# 01_MAIN.net
KiCad netlist of a schematic drawn in Altium Designer
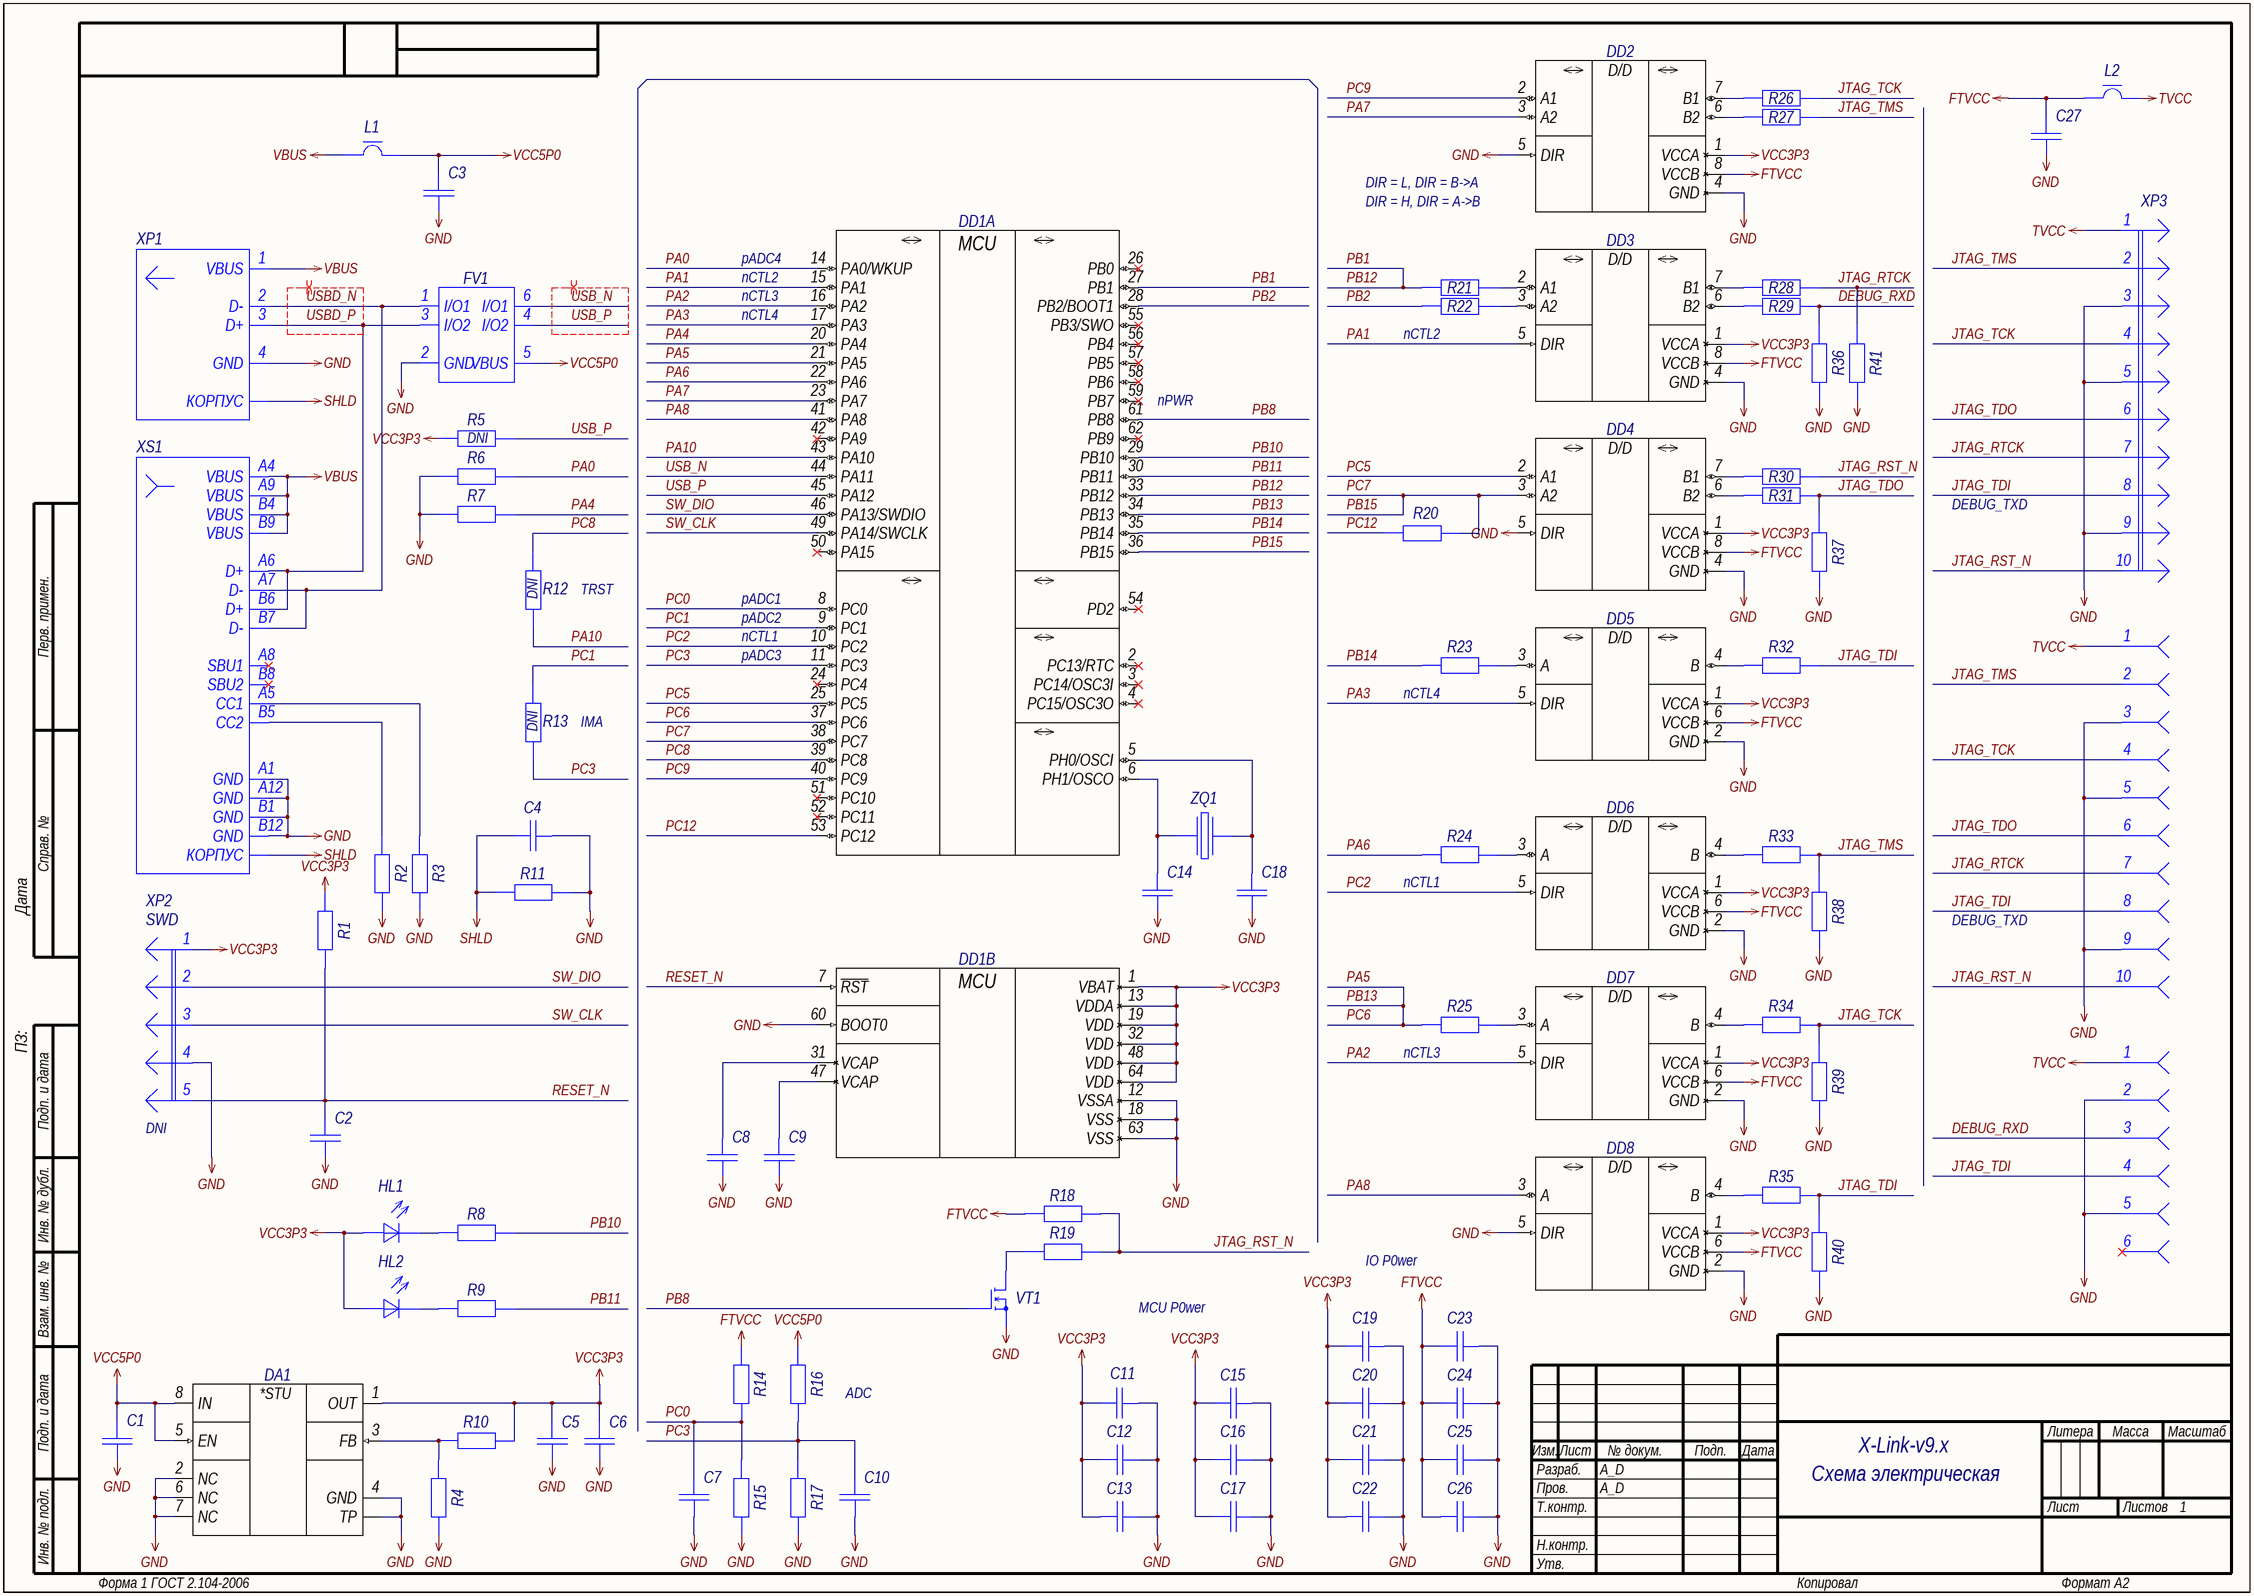
[diagram p0: 01_MAIN.SchDoc]

(export (version "E")
  (design (tool "Eeschema 10.0.6"))
  (components
    (comp (ref "C1")
      (value "Capacitor")
      (footprint "C0402_L")
      (fields
        (field (name "PART NUMBER") "GRM155R61C105KA12D")
        (field (name "VOLTAGE") "16V")
        (field (name "TOLERANCE") "±10%")
        (field (name "PUBLISHER") "Andrew Danich")
      )
      (libsource (lib "ADLib") (part "Capacitor"))
    )
    (comp (ref "C2")
      (value "~")
      (footprint "C0402_L")
      (fields
        (field (name "PART NUMBER") "GCM155R71C104KA55D")
        (field (name "VOLTAGE") "16V")
        (field (name "TOLERANCE") "±10%")
        (field (name "PUBLISHER") "Andrew Danich")
      )
      (libsource (lib "ADLib") (part "Capacitor"))
    )
    (comp (ref "C3")
      (value "Capacitor")
      (footprint "C0603_L")
      (fields
        (field (name "PART NUMBER") "GRM188R61A106KE69D")
        (field (name "VOLTAGE") "10V")
        (field (name "TOLERANCE") "±10%")
        (field (name "PUBLISHER") "Andrew Danich")
      )
      (libsource (lib "ADLib") (part "Capacitor"))
    )
    (comp (ref "C4")
      (value "~")
      (footprint "C0402_L")
      (fields
        (field (name "PART NUMBER") "GCM155R71C104KA55D")
        (field (name "VOLTAGE") "16V")
        (field (name "TOLERANCE") "±10%")
        (field (name "PUBLISHER") "Andrew Danich")
      )
      (libsource (lib "ADLib") (part "Capacitor"))
    )
    (comp (ref "C5")
      (value "Capacitor")
      (footprint "C0402_L")
      (fields
        (field (name "PART NUMBER") "GRM155R60J475ME87D")
        (field (name "VOLTAGE") "6.3V")
        (field (name "TOLERANCE") "±20%")
        (field (name "PUBLISHER") "Andrew Danich")
      )
      (libsource (lib "ADLib") (part "Capacitor"))
    )
    (comp (ref "C6")
      (value "Capacitor")
      (footprint "C0402_L")
      (fields
        (field (name "PART NUMBER") "GRM155R60J475ME87D")
        (field (name "VOLTAGE") "6.3V")
        (field (name "TOLERANCE") "±20%")
        (field (name "PUBLISHER") "Andrew Danich")
      )
      (libsource (lib "ADLib") (part "Capacitor"))
    )
    (comp (ref "C7")
      (value "Capacitor")
      (footprint "C0402_L")
      (fields
        (field (name "PART NUMBER") "GCM155R71E103KA37D")
        (field (name "VOLTAGE") "25V")
        (field (name "TOLERANCE") "±10%")
        (field (name "PUBLISHER") "Andrew Danich")
      )
      (libsource (lib "ADLib") (part "Capacitor"))
    )
    (comp (ref "C8")
      (value "Capacitor")
      (footprint "C0402_L")
      (fields
        (field (name "PART NUMBER") "GRM155D71C225ME11D")
        (field (name "VOLTAGE") "16V")
        (field (name "TOLERANCE") "±20%")
        (field (name "PUBLISHER") "Andrew Danich")
      )
      (libsource (lib "ADLib") (part "Capacitor"))
    )
    (comp (ref "C9")
      (value "Capacitor")
      (footprint "C0402_L")
      (fields
        (field (name "PART NUMBER") "GRM155D71C225ME11D")
        (field (name "VOLTAGE") "16V")
        (field (name "TOLERANCE") "±20%")
        (field (name "PUBLISHER") "Andrew Danich")
      )
      (libsource (lib "ADLib") (part "Capacitor"))
    )
    (comp (ref "C10")
      (value "Capacitor")
      (footprint "C0402_L")
      (fields
        (field (name "PART NUMBER") "GCM155R71E103KA37D")
        (field (name "VOLTAGE") "25V")
        (field (name "TOLERANCE") "±10%")
        (field (name "PUBLISHER") "Andrew Danich")
      )
      (libsource (lib "ADLib") (part "Capacitor"))
    )
    (comp (ref "C11")
      (value "Capacitor")
      (footprint "C0402_L")
      (fields
        (field (name "PART NUMBER") "GRM155R60J475ME87D")
        (field (name "VOLTAGE") "6.3V")
        (field (name "TOLERANCE") "±20%")
        (field (name "PUBLISHER") "Andrew Danich")
      )
      (libsource (lib "ADLib") (part "Capacitor"))
    )
    (comp (ref "C12")
      (value "~")
      (footprint "C0402_L")
      (fields
        (field (name "PART NUMBER") "GCM155R71C104KA55D")
        (field (name "VOLTAGE") "16V")
        (field (name "TOLERANCE") "±10%")
        (field (name "PUBLISHER") "Andrew Danich")
      )
      (libsource (lib "ADLib") (part "Capacitor"))
    )
    (comp (ref "C13")
      (value "~")
      (footprint "C0402_L")
      (fields
        (field (name "PART NUMBER") "GCM155R71C104KA55D")
        (field (name "VOLTAGE") "16V")
        (field (name "TOLERANCE") "±10%")
        (field (name "PUBLISHER") "Andrew Danich")
      )
      (libsource (lib "ADLib") (part "Capacitor"))
    )
    (comp (ref "C14")
      (value "Capacitor")
      (footprint "C0402_L")
      (fields
        (field (name "PART NUMBER") "GRM1555C1H120JA01D")
        (field (name "VOLTAGE") "50V")
        (field (name "TOLERANCE") "±5%")
        (field (name "PUBLISHER") "Andrew Danich")
      )
      (libsource (lib "ADLib") (part "Capacitor"))
    )
    (comp (ref "C15")
      (value "~")
      (footprint "C0402_L")
      (fields
        (field (name "PART NUMBER") "GCM155R71C104KA55D")
        (field (name "VOLTAGE") "16V")
        (field (name "TOLERANCE") "±10%")
        (field (name "PUBLISHER") "Andrew Danich")
      )
      (libsource (lib "ADLib") (part "Capacitor"))
    )
    (comp (ref "C16")
      (value "~")
      (footprint "C0402_L")
      (fields
        (field (name "PART NUMBER") "GCM155R71C104KA55D")
        (field (name "VOLTAGE") "16V")
        (field (name "TOLERANCE") "±10%")
        (field (name "PUBLISHER") "Andrew Danich")
      )
      (libsource (lib "ADLib") (part "Capacitor"))
    )
    (comp (ref "C17")
      (value "~")
      (footprint "C0402_L")
      (fields
        (field (name "PART NUMBER") "GCM155R71C104KA55D")
        (field (name "VOLTAGE") "16V")
        (field (name "TOLERANCE") "±10%")
        (field (name "PUBLISHER") "Andrew Danich")
      )
      (libsource (lib "ADLib") (part "Capacitor"))
    )
    (comp (ref "C18")
      (value "Capacitor")
      (footprint "C0402_L")
      (fields
        (field (name "PART NUMBER") "GRM1555C1H120JA01D")
        (field (name "VOLTAGE") "50V")
        (field (name "TOLERANCE") "±5%")
        (field (name "PUBLISHER") "Andrew Danich")
      )
      (libsource (lib "ADLib") (part "Capacitor"))
    )
    (comp (ref "C19")
      (value "~")
      (footprint "C0402_L")
      (fields
        (field (name "PART NUMBER") "GCM155R71C104KA55D")
        (field (name "VOLTAGE") "16V")
        (field (name "TOLERANCE") "±10%")
        (field (name "PUBLISHER") "Andrew Danich")
      )
      (libsource (lib "ADLib") (part "Capacitor"))
    )
    (comp (ref "C20")
      (value "~")
      (footprint "C0402_L")
      (fields
        (field (name "PART NUMBER") "GCM155R71C104KA55D")
        (field (name "VOLTAGE") "16V")
        (field (name "TOLERANCE") "±10%")
        (field (name "PUBLISHER") "Andrew Danich")
      )
      (libsource (lib "ADLib") (part "Capacitor"))
    )
    (comp (ref "C21")
      (value "~")
      (footprint "C0402_L")
      (fields
        (field (name "PART NUMBER") "GCM155R71C104KA55D")
        (field (name "VOLTAGE") "16V")
        (field (name "TOLERANCE") "±10%")
        (field (name "PUBLISHER") "Andrew Danich")
      )
      (libsource (lib "ADLib") (part "Capacitor"))
    )
    (comp (ref "C22")
      (value "~")
      (footprint "C0402_L")
      (fields
        (field (name "PART NUMBER") "GCM155R71C104KA55D")
        (field (name "VOLTAGE") "16V")
        (field (name "TOLERANCE") "±10%")
        (field (name "PUBLISHER") "Andrew Danich")
      )
      (libsource (lib "ADLib") (part "Capacitor"))
    )
    (comp (ref "C23")
      (value "~")
      (footprint "C0402_L")
      (fields
        (field (name "PART NUMBER") "GCM155R71C104KA55D")
        (field (name "VOLTAGE") "16V")
        (field (name "TOLERANCE") "±10%")
        (field (name "PUBLISHER") "Andrew Danich")
      )
      (libsource (lib "ADLib") (part "Capacitor"))
    )
    (comp (ref "C24")
      (value "~")
      (footprint "C0402_L")
      (fields
        (field (name "PART NUMBER") "GCM155R71C104KA55D")
        (field (name "VOLTAGE") "16V")
        (field (name "TOLERANCE") "±10%")
        (field (name "PUBLISHER") "Andrew Danich")
      )
      (libsource (lib "ADLib") (part "Capacitor"))
    )
    (comp (ref "C25")
      (value "~")
      (footprint "C0402_L")
      (fields
        (field (name "PART NUMBER") "GCM155R71C104KA55D")
        (field (name "VOLTAGE") "16V")
        (field (name "TOLERANCE") "±10%")
        (field (name "PUBLISHER") "Andrew Danich")
      )
      (libsource (lib "ADLib") (part "Capacitor"))
    )
    (comp (ref "C26")
      (value "~")
      (footprint "C0402_L")
      (fields
        (field (name "PART NUMBER") "GCM155R71C104KA55D")
        (field (name "VOLTAGE") "16V")
        (field (name "TOLERANCE") "±10%")
        (field (name "PUBLISHER") "Andrew Danich")
      )
      (libsource (lib "ADLib") (part "Capacitor"))
    )
    (comp (ref "C27")
      (value "Capacitor")
      (footprint "C0402_L")
      (fields
        (field (name "PART NUMBER") "GRM155D71C225ME11D")
        (field (name "VOLTAGE") "16V")
        (field (name "TOLERANCE") "±20%")
        (field (name "PUBLISHER") "Andrew Danich")
      )
      (libsource (lib "ADLib") (part "Capacitor"))
    )
    (comp (ref "DA1")
      (value "TPS73701DRB")
      (footprint "VSON-8_065P300X300X100_N")
      (fields
        (field (name "PART NUMBER") "TPS73701DRBR")
        (field (name "MANUFACTURER") "Texas Instruments")
        (field (name "PUBLISHER") "Andrew Danich")
      )
      (libsource (lib "ADLib") (part "TPS73701DRB"))
    )
    (comp (ref "DD1")
      (value "STM32F205RxTx-Series")
      (footprint "LQFP-64_050P1000X1000X160_N")
      (fields
        (field (name "PART NUMBER") "STM32F205RET6")
        (field (name "MANUFACTURER") "STMicroelectronics")
        (field (name "PUBLISHER") "Andrew Danich")
      )
      (libsource (lib "ADLib") (part "STM32F205RxTx-Series"))
    )
    (comp (ref "DD2")
      (value "SN74LVC2T45DCx-Series")
      (footprint "VSSOP-8_050P200X230X090_N")
      (fields
        (field (name "PART NUMBER") "SN74LVC2T45DCUR")
        (field (name "MANUFACTURER") "Texas Instruments")
        (field (name "PUBLISHER") "Andrew Danich")
      )
      (libsource (lib "ADLib") (part "SN74LVC2T45DCx-Series"))
    )
    (comp (ref "DD3")
      (value "SN74LVC2T45DCx-Series")
      (footprint "VSSOP-8_050P200X230X090_N")
      (fields
        (field (name "PART NUMBER") "SN74LVC2T45DCUR")
        (field (name "MANUFACTURER") "Texas Instruments")
        (field (name "PUBLISHER") "Andrew Danich")
      )
      (libsource (lib "ADLib") (part "SN74LVC2T45DCx-Series"))
    )
    (comp (ref "DD4")
      (value "SN74LVC2T45DCx-Series")
      (footprint "VSSOP-8_050P200X230X090_N")
      (fields
        (field (name "PART NUMBER") "SN74LVC2T45DCUR")
        (field (name "MANUFACTURER") "Texas Instruments")
        (field (name "PUBLISHER") "Andrew Danich")
      )
      (libsource (lib "ADLib") (part "SN74LVC2T45DCx-Series"))
    )
    (comp (ref "DD5")
      (value "74LVC1T45x-Series")
      (footprint "X2-DFN-6_050P140X100X040_N")
      (fields
        (field (name "PART NUMBER") "74LVC1T45FZ4-7")
        (field (name "MANUFACTURER") "Diodes Incorporated")
        (field (name "PUBLISHER") "Andrew Danich")
      )
      (libsource (lib "ADLib") (part "74LVC1T45x-Series"))
    )
    (comp (ref "DD6")
      (value "74LVC1T45x-Series")
      (footprint "X2-DFN-6_050P140X100X040_N")
      (fields
        (field (name "PART NUMBER") "74LVC1T45FZ4-7")
        (field (name "MANUFACTURER") "Diodes Incorporated")
        (field (name "PUBLISHER") "Andrew Danich")
      )
      (libsource (lib "ADLib") (part "74LVC1T45x-Series"))
    )
    (comp (ref "DD7")
      (value "74LVC1T45x-Series")
      (footprint "X2-DFN-6_050P140X100X040_N")
      (fields
        (field (name "PART NUMBER") "74LVC1T45FZ4-7")
        (field (name "MANUFACTURER") "Diodes Incorporated")
        (field (name "PUBLISHER") "Andrew Danich")
      )
      (libsource (lib "ADLib") (part "74LVC1T45x-Series"))
    )
    (comp (ref "DD8")
      (value "74LVC1T45x-Series")
      (footprint "X2-DFN-6_050P140X100X040_N")
      (fields
        (field (name "PART NUMBER") "74LVC1T45FZ4-7")
        (field (name "MANUFACTURER") "Diodes Incorporated")
        (field (name "PUBLISHER") "Andrew Danich")
      )
      (libsource (lib "ADLib") (part "74LVC1T45x-Series"))
    )
    (comp (ref "FV1")
      (value "USBLC6-2x6")
      (footprint "SOT-666_050P160X120X060_N")
      (fields
        (field (name "PART NUMBER") "USBLC6-2P6")
        (field (name "MANUFACTURER") "STMicroelectronics")
        (field (name "PUBLISHER") "Andrew Danich")
      )
      (libsource (lib "ADLib") (part "USBLC6-2x6"))
    )
    (comp (ref "HL1")
      (value "Text")
      (footprint "LD0402")
      (fields
        (field (name "PART NUMBER") "KPHHS-1005QBC-D-V")
        (field (name "MANUFACTURER") "Kingbright")
        (field (name "PUBLISHER") "Andrew Danich")
      )
      (libsource (lib "ADLib") (part "Led-1"))
    )
    (comp (ref "HL2")
      (value "Text")
      (footprint "LD0402")
      (fields
        (field (name "PART NUMBER") "KPHHS-1005QBC-D-V")
        (field (name "MANUFACTURER") "Kingbright")
        (field (name "PUBLISHER") "Andrew Danich")
      )
      (libsource (lib "ADLib") (part "Led-1"))
    )
    (comp (ref "L1")
      (value "FerriteBead")
      (footprint "L0402_L")
      (fields
        (field (name "PART NUMBER") "BLM15PD121SN1D")
        (field (name "TOLERANCE") "±25%")
        (field (name "MANUFACTURER") "Murata")
        (field (name "PUBLISHER") "Andrew Danich")
      )
      (libsource (lib "ADLib") (part "FerriteBead"))
    )
    (comp (ref "L2")
      (value "FerriteBead")
      (footprint "L0402_L")
      (fields
        (field (name "PART NUMBER") "BLM15PD121SN1D")
        (field (name "TOLERANCE") "±25%")
        (field (name "MANUFACTURER") "Murata")
        (field (name "PUBLISHER") "Andrew Danich")
      )
      (libsource (lib "ADLib") (part "FerriteBead"))
    )
    (comp (ref "R1")
      (value "Resistor")
      (footprint "R0402_L")
      (fields
        (field (name "PART NUMBER") "RC0402JR-0710KL")
        (field (name "TOLERANCE") "±5%")
        (field (name "MANUFACTURER") "Yageo")
        (field (name "PUBLISHER") "Andrew Danich")
      )
      (libsource (lib "ADLib") (part "Resistor"))
    )
    (comp (ref "R2")
      (value "Resistor")
      (footprint "R0402_L")
      (fields
        (field (name "PART NUMBER") "RC0402FR-075K1L")
        (field (name "TOLERANCE") "±1%")
        (field (name "MANUFACTURER") "Yageo")
        (field (name "PUBLISHER") "Andrew Danich")
      )
      (libsource (lib "ADLib") (part "Resistor"))
    )
    (comp (ref "R3")
      (value "Resistor")
      (footprint "R0402_L")
      (fields
        (field (name "PART NUMBER") "RC0402FR-075K1L")
        (field (name "TOLERANCE") "±1%")
        (field (name "MANUFACTURER") "Yageo")
        (field (name "PUBLISHER") "Andrew Danich")
      )
      (libsource (lib "ADLib") (part "Resistor"))
    )
    (comp (ref "R4")
      (value "Resistor")
      (footprint "R0402_L")
      (fields
        (field (name "PART NUMBER") "RC0402FR-0712KL")
        (field (name "TOLERANCE") "±1%")
        (field (name "MANUFACTURER") "Yageo")
        (field (name "PUBLISHER") "Andrew Danich")
      )
      (libsource (lib "ADLib") (part "Resistor"))
    )
    (comp (ref "R5")
      (value "Resistor")
      (footprint "R0402_L")
      (fields
        (field (name "PART NUMBER") "RC0402FR-071K6L")
        (field (name "TOLERANCE") "±1%")
        (field (name "MANUFACTURER") "Yageo")
        (field (name "PUBLISHER") "Andrew Danich")
      )
      (libsource (lib "ADLib") (part "Resistor"))
    )
    (comp (ref "R6")
      (value "Resistor")
      (footprint "R0402_L")
      (fields
        (field (name "PART NUMBER") "RC0402JR-070RL")
        (field (name "TOLERANCE") "±5%")
        (field (name "MANUFACTURER") "Yageo")
        (field (name "PUBLISHER") "Andrew Danich")
      )
      (libsource (lib "ADLib") (part "Resistor"))
    )
    (comp (ref "R7")
      (value "Resistor")
      (footprint "R0402_L")
      (fields
        (field (name "PART NUMBER") "RC0402JR-070RL")
        (field (name "TOLERANCE") "±5%")
        (field (name "MANUFACTURER") "Yageo")
        (field (name "PUBLISHER") "Andrew Danich")
      )
      (libsource (lib "ADLib") (part "Resistor"))
    )
    (comp (ref "R8")
      (value "Resistor")
      (footprint "R0402_L")
      (fields
        (field (name "PART NUMBER") "RC0402JR-071KL")
        (field (name "TOLERANCE") "±5%")
        (field (name "MANUFACTURER") "Yageo")
        (field (name "PUBLISHER") "Andrew Danich")
      )
      (libsource (lib "ADLib") (part "Resistor"))
    )
    (comp (ref "R9")
      (value "Resistor")
      (footprint "R0402_L")
      (fields
        (field (name "PART NUMBER") "RC0402JR-071KL")
        (field (name "TOLERANCE") "±5%")
        (field (name "MANUFACTURER") "Yageo")
        (field (name "PUBLISHER") "Andrew Danich")
      )
      (libsource (lib "ADLib") (part "Resistor"))
    )
    (comp (ref "R10")
      (value "Resistor")
      (footprint "R0402_L")
      (fields
        (field (name "PART NUMBER") "RC0402FR-0722K1L")
        (field (name "TOLERANCE") "±1%")
        (field (name "MANUFACTURER") "Yageo")
        (field (name "PUBLISHER") "Andrew Danich")
      )
      (libsource (lib "ADLib") (part "Resistor"))
    )
    (comp (ref "R11")
      (value "~")
      (footprint "R0402_L")
      (fields
        (field (name "PART NUMBER") "RC0402JR-07100KL")
        (field (name "TOLERANCE") "±5%")
        (field (name "MANUFACTURER") "Yageo")
        (field (name "PUBLISHER") "Andrew Danich")
      )
      (libsource (lib "ADLib") (part "Resistor"))
    )
    (comp (ref "R12")
      (value "Resistor")
      (footprint "R0402_L")
      (fields
        (field (name "PART NUMBER") "RC0402JR-070RL")
        (field (name "TOLERANCE") "±5%")
        (field (name "MANUFACTURER") "Yageo")
        (field (name "PUBLISHER") "Andrew Danich")
      )
      (libsource (lib "ADLib") (part "Resistor"))
    )
    (comp (ref "R13")
      (value "Resistor")
      (footprint "R0402_L")
      (fields
        (field (name "PART NUMBER") "RC0402JR-070RL")
        (field (name "TOLERANCE") "±5%")
        (field (name "MANUFACTURER") "Yageo")
        (field (name "PUBLISHER") "Andrew Danich")
      )
      (libsource (lib "ADLib") (part "Resistor"))
    )
    (comp (ref "R14")
      (value "Resistor")
      (footprint "R0402_L")
      (fields
        (field (name "PART NUMBER") "RC0402FR-0710KL")
        (field (name "TOLERANCE") "±1%")
        (field (name "MANUFACTURER") "Yageo")
        (field (name "PUBLISHER") "Andrew Danich")
      )
      (libsource (lib "ADLib") (part "Resistor"))
    )
    (comp (ref "R15")
      (value "Resistor")
      (footprint "R0402_L")
      (fields
        (field (name "PART NUMBER") "RC0402FR-0710KL")
        (field (name "TOLERANCE") "±1%")
        (field (name "MANUFACTURER") "Yageo")
        (field (name "PUBLISHER") "Andrew Danich")
      )
      (libsource (lib "ADLib") (part "Resistor"))
    )
    (comp (ref "R16")
      (value "Resistor")
      (footprint "R0402_L")
      (fields
        (field (name "PART NUMBER") "RC0402FR-0710KL")
        (field (name "TOLERANCE") "±1%")
        (field (name "MANUFACTURER") "Yageo")
        (field (name "PUBLISHER") "Andrew Danich")
      )
      (libsource (lib "ADLib") (part "Resistor"))
    )
    (comp (ref "R17")
      (value "Resistor")
      (footprint "R0402_L")
      (fields
        (field (name "PART NUMBER") "RC0402FR-0710KL")
        (field (name "TOLERANCE") "±1%")
        (field (name "MANUFACTURER") "Yageo")
        (field (name "PUBLISHER") "Andrew Danich")
      )
      (libsource (lib "ADLib") (part "Resistor"))
    )
    (comp (ref "R18")
      (value "Resistor")
      (footprint "R0402_L")
      (fields
        (field (name "PART NUMBER") "RC0402JR-074K7L")
        (field (name "TOLERANCE") "±5%")
        (field (name "MANUFACTURER") "Yageo")
        (field (name "PUBLISHER") "Andrew Danich")
      )
      (libsource (lib "ADLib") (part "Resistor"))
    )
    (comp (ref "R19")
      (value "Resistor")
      (footprint "R0402_L")
      (fields
        (field (name "PART NUMBER") "RC0402JR-0751RL")
        (field (name "TOLERANCE") "±5%")
        (field (name "MANUFACTURER") "Yageo")
        (field (name "PUBLISHER") "Andrew Danich")
      )
      (libsource (lib "ADLib") (part "Resistor"))
    )
    (comp (ref "R20")
      (value "Resistor")
      (footprint "R0402_L")
      (fields
        (field (name "PART NUMBER") "RC0402JR-070RL")
        (field (name "TOLERANCE") "±5%")
        (field (name "MANUFACTURER") "Yageo")
        (field (name "PUBLISHER") "Andrew Danich")
      )
      (libsource (lib "ADLib") (part "Resistor"))
    )
    (comp (ref "R21")
      (value "Resistor")
      (footprint "R0402_L")
      (fields
        (field (name "PART NUMBER") "RC0402JR-07430RL")
        (field (name "TOLERANCE") "±5%")
        (field (name "MANUFACTURER") "Yageo")
        (field (name "PUBLISHER") "Andrew Danich")
      )
      (libsource (lib "ADLib") (part "Resistor"))
    )
    (comp (ref "R22")
      (value "Resistor")
      (footprint "R0402_L")
      (fields
        (field (name "PART NUMBER") "RC0402JR-07430RL")
        (field (name "TOLERANCE") "±5%")
        (field (name "MANUFACTURER") "Yageo")
        (field (name "PUBLISHER") "Andrew Danich")
      )
      (libsource (lib "ADLib") (part "Resistor"))
    )
    (comp (ref "R23")
      (value "Resistor")
      (footprint "R0402_L")
      (fields
        (field (name "PART NUMBER") "RC0402JR-07430RL")
        (field (name "TOLERANCE") "±5%")
        (field (name "MANUFACTURER") "Yageo")
        (field (name "PUBLISHER") "Andrew Danich")
      )
      (libsource (lib "ADLib") (part "Resistor"))
    )
    (comp (ref "R24")
      (value "Resistor")
      (footprint "R0402_L")
      (fields
        (field (name "PART NUMBER") "RC0402JR-07430RL")
        (field (name "TOLERANCE") "±5%")
        (field (name "MANUFACTURER") "Yageo")
        (field (name "PUBLISHER") "Andrew Danich")
      )
      (libsource (lib "ADLib") (part "Resistor"))
    )
    (comp (ref "R25")
      (value "Resistor")
      (footprint "R0402_L")
      (fields
        (field (name "PART NUMBER") "RC0402JR-07430RL")
        (field (name "TOLERANCE") "±5%")
        (field (name "MANUFACTURER") "Yageo")
        (field (name "PUBLISHER") "Andrew Danich")
      )
      (libsource (lib "ADLib") (part "Resistor"))
    )
    (comp (ref "R26")
      (value "Resistor")
      (footprint "R0402_L")
      (fields
        (field (name "PART NUMBER") "RC0402JR-07430RL")
        (field (name "TOLERANCE") "±5%")
        (field (name "MANUFACTURER") "Yageo")
        (field (name "PUBLISHER") "Andrew Danich")
      )
      (libsource (lib "ADLib") (part "Resistor"))
    )
    (comp (ref "R27")
      (value "Resistor")
      (footprint "R0402_L")
      (fields
        (field (name "PART NUMBER") "RC0402JR-07430RL")
        (field (name "TOLERANCE") "±5%")
        (field (name "MANUFACTURER") "Yageo")
        (field (name "PUBLISHER") "Andrew Danich")
      )
      (libsource (lib "ADLib") (part "Resistor"))
    )
    (comp (ref "R28")
      (value "Resistor")
      (footprint "R0402_L")
      (fields
        (field (name "PART NUMBER") "RC0402JR-07100RL")
        (field (name "TOLERANCE") "±5%")
        (field (name "MANUFACTURER") "Yageo")
        (field (name "PUBLISHER") "Andrew Danich")
      )
      (libsource (lib "ADLib") (part "Resistor"))
    )
    (comp (ref "R29")
      (value "Resistor")
      (footprint "R0402_L")
      (fields
        (field (name "PART NUMBER") "RC0402JR-07100RL")
        (field (name "TOLERANCE") "±5%")
        (field (name "MANUFACTURER") "Yageo")
        (field (name "PUBLISHER") "Andrew Danich")
      )
      (libsource (lib "ADLib") (part "Resistor"))
    )
    (comp (ref "R30")
      (value "Resistor")
      (footprint "R0402_L")
      (fields
        (field (name "PART NUMBER") "RC0402JR-07430RL")
        (field (name "TOLERANCE") "±5%")
        (field (name "MANUFACTURER") "Yageo")
        (field (name "PUBLISHER") "Andrew Danich")
      )
      (libsource (lib "ADLib") (part "Resistor"))
    )
    (comp (ref "R31")
      (value "Resistor")
      (footprint "R0402_L")
      (fields
        (field (name "PART NUMBER") "RC0402JR-07430RL")
        (field (name "TOLERANCE") "±5%")
        (field (name "MANUFACTURER") "Yageo")
        (field (name "PUBLISHER") "Andrew Danich")
      )
      (libsource (lib "ADLib") (part "Resistor"))
    )
    (comp (ref "R32")
      (value "Resistor")
      (footprint "R0402_L")
      (fields
        (field (name "PART NUMBER") "RC0402JR-07100RL")
        (field (name "TOLERANCE") "±5%")
        (field (name "MANUFACTURER") "Yageo")
        (field (name "PUBLISHER") "Andrew Danich")
      )
      (libsource (lib "ADLib") (part "Resistor"))
    )
    (comp (ref "R33")
      (value "Resistor")
      (footprint "R0402_L")
      (fields
        (field (name "PART NUMBER") "RC0402JR-07100RL")
        (field (name "TOLERANCE") "±5%")
        (field (name "MANUFACTURER") "Yageo")
        (field (name "PUBLISHER") "Andrew Danich")
      )
      (libsource (lib "ADLib") (part "Resistor"))
    )
    (comp (ref "R34")
      (value "Resistor")
      (footprint "R0402_L")
      (fields
        (field (name "PART NUMBER") "RC0402JR-07100RL")
        (field (name "TOLERANCE") "±5%")
        (field (name "MANUFACTURER") "Yageo")
        (field (name "PUBLISHER") "Andrew Danich")
      )
      (libsource (lib "ADLib") (part "Resistor"))
    )
    (comp (ref "R35")
      (value "Resistor")
      (footprint "R0402_L")
      (fields
        (field (name "PART NUMBER") "RC0402JR-07430RL")
        (field (name "TOLERANCE") "±5%")
        (field (name "MANUFACTURER") "Yageo")
        (field (name "PUBLISHER") "Andrew Danich")
      )
      (libsource (lib "ADLib") (part "Resistor"))
    )
    (comp (ref "R36")
      (value "Resistor")
      (footprint "R0402_L")
      (fields
        (field (name "PART NUMBER") "RC0402JR-07200KL")
        (field (name "TOLERANCE") "±5%")
        (field (name "MANUFACTURER") "Yageo")
        (field (name "PUBLISHER") "Andrew Danich")
      )
      (libsource (lib "ADLib") (part "Resistor"))
    )
    (comp (ref "R37")
      (value "Resistor")
      (footprint "R0402_L")
      (fields
        (field (name "PART NUMBER") "RC0402JR-07200KL")
        (field (name "TOLERANCE") "±5%")
        (field (name "MANUFACTURER") "Yageo")
        (field (name "PUBLISHER") "Andrew Danich")
      )
      (libsource (lib "ADLib") (part "Resistor"))
    )
    (comp (ref "R38")
      (value "Resistor")
      (footprint "R0402_L")
      (fields
        (field (name "PART NUMBER") "RC0402JR-07200KL")
        (field (name "TOLERANCE") "±5%")
        (field (name "MANUFACTURER") "Yageo")
        (field (name "PUBLISHER") "Andrew Danich")
      )
      (libsource (lib "ADLib") (part "Resistor"))
    )
    (comp (ref "R39")
      (value "Resistor")
      (footprint "R0402_L")
      (fields
        (field (name "PART NUMBER") "RC0402JR-07200KL")
        (field (name "TOLERANCE") "±5%")
        (field (name "MANUFACTURER") "Yageo")
        (field (name "PUBLISHER") "Andrew Danich")
      )
      (libsource (lib "ADLib") (part "Resistor"))
    )
    (comp (ref "R40")
      (value "Resistor")
      (footprint "R0402_L")
      (fields
        (field (name "PART NUMBER") "RC0402JR-07200KL")
        (field (name "TOLERANCE") "±5%")
        (field (name "MANUFACTURER") "Yageo")
        (field (name "PUBLISHER") "Andrew Danich")
      )
      (libsource (lib "ADLib") (part "Resistor"))
    )
    (comp (ref "R41")
      (value "Resistor")
      (footprint "R0402_L")
      (fields
        (field (name "PART NUMBER") "RC0402JR-07200KL")
        (field (name "TOLERANCE") "±5%")
        (field (name "MANUFACTURER") "Yageo")
        (field (name "PUBLISHER") "Andrew Danich")
      )
      (libsource (lib "ADLib") (part "Resistor"))
    )
    (comp (ref "VT1")
      (value "MOSFET-N")
      (footprint "SOT-883B_035P060X100X040_N")
      (fields
        (field (name "PART NUMBER") "NX3008NBKMB")
        (field (name "MANUFACTURER") "NXP Semiconductors")
        (field (name "PUBLISHER") "Andrew Danich")
      )
      (libsource (lib "ADLib") (part "MOSFET-N"))
    )
    (comp (ref "XP1")
      (value "Text")
      (footprint "DS1097")
      (fields
        (field (name "PART NUMBER") "DS1097-B")
        (field (name "MANUFACTURER") "Connfly Electronic Co., Ltd")
        (field (name "PUBLISHER") "Andrew Danich")
      )
      (libsource (lib "ADLib") (part "Con-5-M-USB"))
    )
    (comp (ref "XP2")
      (value "SWD")
      (footprint "PLS-5")
      (fields (field (name "PART NUMBER") "PLS-5") (field (name "PUBLISHER") "Andrew Danich"))
      (libsource (lib "ADLib") (part "Con-5-M"))
    )
    (comp (ref "XP3")
      (value "JTAG")
      (footprint "IDC-10MR")
      (fields (field (name "PART NUMBER") "IDC-10MR") (field (name "PUBLISHER") "Andrew Danich"))
      (libsource (lib "ADLib") (part "Con-10-M"))
    )
    (comp (ref "XS1")
      (value "Text")
      (footprint "U262-161N-4BVC11")
      (fields
        (field (name "PART NUMBER") "U262-161N-4BVC11")
        (field (name "MANUFACTURER") "XKB Enterprise")
        (field (name "PUBLISHER") "Andrew Danich")
      )
      (libsource (lib "ADLib") (part "Con-USB_C-F-16P"))
    )
    (comp (ref "XS2")
      (value "JTAG-FFC")
      (footprint "XF2M-1015-1A")
      (fields
        (field (name "PART NUMBER") "XF2M-1015-1A")
        (field (name "MANUFACTURER") "Omron Electronics")
        (field (name "PUBLISHER") "Viktor Klishin")
      )
      (libsource (lib "ADLib") (part "Con-10-F_S"))
    )
    (comp (ref "XS3")
      (value "SWO")
      (footprint "XF2M-0615-1A")
      (fields
        (field (name "PART NUMBER") "XF2M-0615-1A")
        (field (name "MANUFACTURER") "Omron Electronics")
        (field (name "PUBLISHER") "Viktor Klishin")
      )
      (libsource (lib "ADLib") (part "Con-6-F_S"))
    )
    (comp (ref "ZQ1")
      (value "Crystal")
      (footprint "SMD 5x3.2mm")
      (fields (field (name "PART NUMBER") "AB-12.000MALE-T") (field (name "PUBLISHER") "Andrew Danich"))
      (libsource (lib "ADLib") (part "Crystal"))
    )
  )
  (nets
    (net (code "1") (name "/DEBUG_RXD") (class "Default")
      (node (ref "R29") (pin "2") (pinfunction "2_2") (pintype "passive"))
      (node (ref "R36") (pin "2") (pinfunction "2_2") (pintype "passive"))
      (node (ref "XS3") (pin "3") (pintype "passive"))
    )
    (net (code "2") (name "/JTAG_RST_N") (class "Default")
      (node (ref "R18") (pin "2") (pinfunction "2_2") (pintype "passive"))
      (node (ref "R19") (pin "2") (pinfunction "2_2") (pintype "passive"))
      (node (ref "R30") (pin "2") (pinfunction "2_2") (pintype "passive"))
      (node (ref "XP3") (pin "10") (pintype "passive"))
      (node (ref "XS2") (pin "10") (pintype "passive"))
    )
    (net (code "3") (name "/JTAG_RTCK") (class "Default")
      (node (ref "R28") (pin "2") (pinfunction "2_2") (pintype "passive"))
      (node (ref "R41") (pin "2") (pinfunction "2_2") (pintype "passive"))
      (node (ref "XP3") (pin "7") (pintype "passive"))
      (node (ref "XS2") (pin "7") (pintype "passive"))
    )
    (net (code "4") (name "/JTAG_TCK") (class "Default")
      (node (ref "R26") (pin "2") (pinfunction "2_2") (pintype "passive"))
      (node (ref "R34") (pin "2") (pinfunction "2_2") (pintype "passive"))
      (node (ref "R39") (pin "2") (pinfunction "2_2") (pintype "passive"))
      (node (ref "XP3") (pin "4") (pintype "passive"))
      (node (ref "XS2") (pin "4") (pintype "passive"))
    )
    (net (code "5") (name "/JTAG_TDI") (class "Default")
      (node (ref "R32") (pin "2") (pinfunction "2_2") (pintype "passive"))
      (node (ref "R35") (pin "2") (pinfunction "2_2") (pintype "passive"))
      (node (ref "R40") (pin "2") (pinfunction "2_2") (pintype "passive"))
      (node (ref "XP3") (pin "8") (pintype "passive"))
      (node (ref "XS2") (pin "8") (pintype "passive"))
      (node (ref "XS3") (pin "4") (pintype "passive"))
    )
    (net (code "6") (name "/JTAG_TDO") (class "Default")
      (node (ref "R31") (pin "2") (pinfunction "2_2") (pintype "passive"))
      (node (ref "R37") (pin "2") (pinfunction "2_2") (pintype "passive"))
      (node (ref "XP3") (pin "6") (pintype "passive"))
      (node (ref "XS2") (pin "6") (pintype "passive"))
    )
    (net (code "7") (name "/JTAG_TMS") (class "Default")
      (node (ref "R27") (pin "2") (pinfunction "2_2") (pintype "passive"))
      (node (ref "R33") (pin "2") (pinfunction "2_2") (pintype "passive"))
      (node (ref "R38") (pin "2") (pinfunction "2_2") (pintype "passive"))
      (node (ref "XP3") (pin "2") (pintype "passive"))
      (node (ref "XS2") (pin "2") (pintype "passive"))
    )
    (net (code "8") (name "/PA0") (class "Default")
      (node (ref "DD1") (pin "14") (pinfunction "PA0/WKUP_14") (pintype "bidirectional"))
      (node (ref "R6") (pin "2") (pinfunction "2_2") (pintype "passive"))
    )
    (net (code "9") (name "/PA1") (class "Default")
      (node (ref "DD1") (pin "15") (pinfunction "PA1_15") (pintype "bidirectional"))
      (node (ref "DD3") (pin "5") (pinfunction "DIR_5") (pintype "input"))
    )
    (net (code "10") (name "/PA2") (class "Default")
      (node (ref "DD1") (pin "16") (pinfunction "PA2_16") (pintype "bidirectional"))
      (node (ref "DD7") (pin "5") (pinfunction "DIR_5") (pintype "input"))
    )
    (net (code "11") (name "/PA3") (class "Default")
      (node (ref "DD1") (pin "17") (pinfunction "PA3_17") (pintype "bidirectional"))
      (node (ref "DD5") (pin "5") (pinfunction "DIR_5") (pintype "input"))
    )
    (net (code "12") (name "/PA4") (class "Default")
      (node (ref "DD1") (pin "20") (pinfunction "PA4_20") (pintype "bidirectional"))
      (node (ref "R7") (pin "2") (pinfunction "2_2") (pintype "passive"))
    )
    (net (code "13") (name "/PA5") (class "Default")
      (node (ref "DD1") (pin "21") (pinfunction "PA5_21") (pintype "bidirectional"))
      (node (ref "DD1") (pin "34") (pinfunction "PB13_34") (pintype "bidirectional"))
      (node (ref "DD1") (pin "37") (pinfunction "PC6_37") (pintype "bidirectional"))
      (node (ref "R25") (pin "1") (pinfunction "1_1") (pintype "passive"))
    )
    (net (code "14") (name "/PA6") (class "Default")
      (node (ref "DD1") (pin "22") (pinfunction "PA6_22") (pintype "bidirectional"))
      (node (ref "R24") (pin "1") (pinfunction "1_1") (pintype "passive"))
    )
    (net (code "15") (name "/PA7") (class "Default")
      (node (ref "DD1") (pin "23") (pinfunction "PA7_23") (pintype "bidirectional"))
      (node (ref "DD2") (pin "3") (pinfunction "A2_3") (pintype "bidirectional"))
    )
    (net (code "16") (name "/PA8") (class "Default")
      (node (ref "DD1") (pin "41") (pinfunction "PA8_41") (pintype "bidirectional"))
      (node (ref "DD8") (pin "3") (pinfunction "A_3") (pintype "bidirectional"))
    )
    (net (code "17") (name "/PA10") (class "Default")
      (node (ref "DD1") (pin "43") (pinfunction "PA10_43") (pintype "bidirectional"))
      (node (ref "R12") (pin "1") (pinfunction "1_1") (pintype "passive"))
    )
    (net (code "18") (name "/PB1") (class "Default")
      (node (ref "DD1") (pin "27") (pinfunction "PB1_27") (pintype "bidirectional"))
      (node (ref "DD1") (pin "33") (pinfunction "PB12_33") (pintype "bidirectional"))
      (node (ref "R21") (pin "1") (pinfunction "1_1") (pintype "passive"))
    )
    (net (code "19") (name "/PB2") (class "Default")
      (node (ref "DD1") (pin "28") (pinfunction "PB2/BOOT1_28") (pintype "bidirectional"))
      (node (ref "R22") (pin "1") (pinfunction "1_1") (pintype "passive"))
    )
    (net (code "20") (name "/PB8") (class "Default")
      (node (ref "DD1") (pin "61") (pinfunction "PB8_61") (pintype "bidirectional"))
      (node (ref "VT1") (pin "1") (pinfunction "G_1") (pintype "passive"))
    )
    (net (code "21") (name "/PB10") (class "Default")
      (node (ref "DD1") (pin "29") (pinfunction "PB10_29") (pintype "bidirectional"))
      (node (ref "R8") (pin "2") (pinfunction "2_2") (pintype "passive"))
    )
    (net (code "22") (name "/PB11") (class "Default")
      (node (ref "DD1") (pin "30") (pinfunction "PB11_30") (pintype "bidirectional"))
      (node (ref "R9") (pin "2") (pinfunction "2_2") (pintype "passive"))
    )
    (net (code "23") (name "/PB14") (class "Default")
      (node (ref "DD1") (pin "35") (pinfunction "PB14_35") (pintype "bidirectional"))
      (node (ref "R23") (pin "1") (pinfunction "1_1") (pintype "passive"))
    )
    (net (code "24") (name "/PB15") (class "Default")
      (node (ref "DD1") (pin "36") (pinfunction "PB15_36") (pintype "bidirectional"))
      (node (ref "DD1") (pin "38") (pinfunction "PC7_38") (pintype "bidirectional"))
      (node (ref "DD4") (pin "3") (pinfunction "A2_3") (pintype "bidirectional"))
      (node (ref "R20") (pin "2") (pinfunction "2_2") (pintype "passive"))
    )
    (net (code "25") (name "/PC0") (class "Default")
      (node (ref "C7") (pin "1") (pinfunction "1_1") (pintype "passive"))
      (node (ref "DD1") (pin "8") (pinfunction "PC0_8") (pintype "bidirectional"))
      (node (ref "R14") (pin "1") (pinfunction "1_1") (pintype "passive"))
      (node (ref "R15") (pin "2") (pinfunction "2_2") (pintype "passive"))
    )
    (net (code "26") (name "/PC1") (class "Default")
      (node (ref "DD1") (pin "9") (pinfunction "PC1_9") (pintype "bidirectional"))
      (node (ref "R13") (pin "2") (pinfunction "2_2") (pintype "passive"))
    )
    (net (code "27") (name "/PC2") (class "Default")
      (node (ref "DD1") (pin "10") (pinfunction "PC2_10") (pintype "bidirectional"))
      (node (ref "DD6") (pin "5") (pinfunction "DIR_5") (pintype "input"))
    )
    (net (code "28") (name "/PC3") (class "Default")
      (node (ref "C10") (pin "1") (pinfunction "1_1") (pintype "passive"))
      (node (ref "DD1") (pin "11") (pinfunction "PC3_11") (pintype "bidirectional"))
      (node (ref "R13") (pin "1") (pinfunction "1_1") (pintype "passive"))
      (node (ref "R16") (pin "1") (pinfunction "1_1") (pintype "passive"))
      (node (ref "R17") (pin "2") (pinfunction "2_2") (pintype "passive"))
    )
    (net (code "29") (name "/PC5") (class "Default")
      (node (ref "DD1") (pin "25") (pinfunction "PC5_25") (pintype "bidirectional"))
      (node (ref "DD4") (pin "2") (pinfunction "A1_2") (pintype "bidirectional"))
    )
    (net (code "30") (name "/PC8") (class "Default")
      (node (ref "DD1") (pin "39") (pinfunction "PC8_39") (pintype "bidirectional"))
      (node (ref "R12") (pin "2") (pinfunction "2_2") (pintype "passive"))
    )
    (net (code "31") (name "/PC9") (class "Default")
      (node (ref "DD1") (pin "40") (pinfunction "PC9_40") (pintype "bidirectional"))
      (node (ref "DD2") (pin "2") (pinfunction "A1_2") (pintype "bidirectional"))
    )
    (net (code "32") (name "/PC12") (class "Default")
      (node (ref "DD1") (pin "53") (pinfunction "PC12_53") (pintype "bidirectional"))
      (node (ref "R20") (pin "1") (pinfunction "1_1") (pintype "passive"))
    )
    (net (code "33") (name "/RESET_N") (class "Default")
      (node (ref "C2") (pin "1") (pinfunction "1_1") (pintype "passive"))
      (node (ref "DD1") (pin "7") (pinfunction "~{RST}_7") (pintype "input"))
      (node (ref "R1") (pin "1") (pinfunction "1_1") (pintype "passive"))
      (node (ref "XP2") (pin "5") (pintype "passive"))
    )
    (net (code "34") (name "/SW_CLK") (class "Default")
      (node (ref "DD1") (pin "49") (pinfunction "PA14/SWCLK_49") (pintype "bidirectional"))
      (node (ref "XP2") (pin "3") (pintype "passive"))
    )
    (net (code "35") (name "/SW_DIO") (class "Default")
      (node (ref "DD1") (pin "46") (pinfunction "PA13/SWDIO_46") (pintype "bidirectional"))
      (node (ref "XP2") (pin "2") (pintype "passive"))
    )
    (net (code "36") (name "/USBD_N") (class "Default")
      (node (ref "FV1") (pin "1") (pinfunction "I/O1_1") (pintype "passive"))
      (node (ref "XP1") (pin "2") (pinfunction "D-_2") (pintype "passive"))
      (node (ref "XS1") (pin "A7") (pinfunction "D-_A7") (pintype "passive"))
      (node (ref "XS1") (pin "B7") (pinfunction "D-_B7") (pintype "passive"))
    )
    (net (code "37") (name "/USBD_P") (class "Default")
      (node (ref "FV1") (pin "3") (pinfunction "I/O2_3") (pintype "passive"))
      (node (ref "XP1") (pin "3") (pinfunction "D+_3") (pintype "passive"))
      (node (ref "XS1") (pin "A6") (pinfunction "D+_A6") (pintype "passive"))
      (node (ref "XS1") (pin "B6") (pinfunction "D+_B6") (pintype "passive"))
    )
    (net (code "38") (name "/USB_N") (class "Default")
      (node (ref "DD1") (pin "44") (pinfunction "PA11_44") (pintype "bidirectional"))
      (node (ref "FV1") (pin "6") (pinfunction "I/O1_6") (pintype "passive"))
    )
    (net (code "39") (name "/USB_P") (class "Default")
      (node (ref "DD1") (pin "45") (pinfunction "PA12_45") (pintype "bidirectional"))
      (node (ref "FV1") (pin "4") (pinfunction "I/O2_4") (pintype "passive"))
      (node (ref "R5") (pin "2") (pinfunction "2_2") (pintype "passive"))
    )
    (net (code "40") (name "FTVCC") (class "Default")
      (node (ref "C23") (pin "1") (pinfunction "1_1") (pintype "passive"))
      (node (ref "C24") (pin "1") (pinfunction "1_1") (pintype "passive"))
      (node (ref "C25") (pin "1") (pinfunction "1_1") (pintype "passive"))
      (node (ref "C26") (pin "1") (pinfunction "1_1") (pintype "passive"))
      (node (ref "C27") (pin "2") (pinfunction "2_2") (pintype "passive"))
      (node (ref "DD2") (pin "8") (pinfunction "VCCB_8") (pintype "power_in"))
      (node (ref "DD3") (pin "8") (pinfunction "VCCB_8") (pintype "power_in"))
      (node (ref "DD4") (pin "8") (pinfunction "VCCB_8") (pintype "power_in"))
      (node (ref "DD5") (pin "6") (pinfunction "VCCB_6") (pintype "power_in"))
      (node (ref "DD6") (pin "6") (pinfunction "VCCB_6") (pintype "power_in"))
      (node (ref "DD7") (pin "6") (pinfunction "VCCB_6") (pintype "power_in"))
      (node (ref "DD8") (pin "6") (pinfunction "VCCB_6") (pintype "power_in"))
      (node (ref "L2") (pin "1") (pinfunction "1_1") (pintype "passive"))
      (node (ref "R14") (pin "2") (pinfunction "2_2") (pintype "passive"))
      (node (ref "R18") (pin "1") (pinfunction "1_1") (pintype "passive"))
    )
    (net (code "41") (name "GND") (class "Default")
      (node (ref "C1") (pin "1") (pinfunction "1_1") (pintype "passive"))
      (node (ref "C10") (pin "2") (pinfunction "2_2") (pintype "passive"))
      (node (ref "C11") (pin "1") (pinfunction "1_1") (pintype "passive"))
      (node (ref "C12") (pin "2") (pinfunction "2_2") (pintype "passive"))
      (node (ref "C13") (pin "2") (pinfunction "2_2") (pintype "passive"))
      (node (ref "C14") (pin "1") (pinfunction "1_1") (pintype "passive"))
      (node (ref "C15") (pin "2") (pinfunction "2_2") (pintype "passive"))
      (node (ref "C16") (pin "2") (pinfunction "2_2") (pintype "passive"))
      (node (ref "C17") (pin "2") (pinfunction "2_2") (pintype "passive"))
      (node (ref "C18") (pin "1") (pinfunction "1_1") (pintype "passive"))
      (node (ref "C19") (pin "2") (pinfunction "2_2") (pintype "passive"))
      (node (ref "C2") (pin "2") (pinfunction "2_2") (pintype "passive"))
      (node (ref "C20") (pin "2") (pinfunction "2_2") (pintype "passive"))
      (node (ref "C21") (pin "2") (pinfunction "2_2") (pintype "passive"))
      (node (ref "C22") (pin "2") (pinfunction "2_2") (pintype "passive"))
      (node (ref "C23") (pin "2") (pinfunction "2_2") (pintype "passive"))
      (node (ref "C24") (pin "2") (pinfunction "2_2") (pintype "passive"))
      (node (ref "C25") (pin "2") (pinfunction "2_2") (pintype "passive"))
      (node (ref "C26") (pin "2") (pinfunction "2_2") (pintype "passive"))
      (node (ref "C27") (pin "1") (pinfunction "1_1") (pintype "passive"))
      (node (ref "C3") (pin "1") (pinfunction "1_1") (pintype "passive"))
      (node (ref "C4") (pin "1") (pinfunction "1_1") (pintype "passive"))
      (node (ref "C5") (pin "1") (pinfunction "1_1") (pintype "passive"))
      (node (ref "C6") (pin "1") (pinfunction "1_1") (pintype "passive"))
      (node (ref "C7") (pin "2") (pinfunction "2_2") (pintype "passive"))
      (node (ref "C8") (pin "1") (pinfunction "1_1") (pintype "passive"))
      (node (ref "C9") (pin "1") (pinfunction "1_1") (pintype "passive"))
      (node (ref "DA1") (pin "2") (pinfunction "NC_2") (pintype "passive"))
      (node (ref "DA1") (pin "4") (pinfunction "GND_4") (pintype "power_in"))
      (node (ref "DA1") (pin "6") (pinfunction "NC_6") (pintype "passive"))
      (node (ref "DA1") (pin "7") (pinfunction "NC_7") (pintype "passive"))
      (node (ref "DA1") (pin "TP") (pinfunction "TP_TP") (pintype "passive"))
      (node (ref "DD1") (pin "12") (pinfunction "VSSA_12") (pintype "power_in"))
      (node (ref "DD1") (pin "18") (pinfunction "VSS_18") (pintype "power_in"))
      (node (ref "DD1") (pin "60") (pinfunction "BOOT0_60") (pintype "input"))
      (node (ref "DD1") (pin "63") (pinfunction "VSS_63") (pintype "power_in"))
      (node (ref "DD2") (pin "4") (pinfunction "GND_4") (pintype "power_in"))
      (node (ref "DD2") (pin "5") (pinfunction "DIR_5") (pintype "input"))
      (node (ref "DD3") (pin "4") (pinfunction "GND_4") (pintype "power_in"))
      (node (ref "DD4") (pin "4") (pinfunction "GND_4") (pintype "power_in"))
      (node (ref "DD4") (pin "5") (pinfunction "DIR_5") (pintype "input"))
      (node (ref "DD5") (pin "2") (pinfunction "GND_2") (pintype "power_in"))
      (node (ref "DD6") (pin "2") (pinfunction "GND_2") (pintype "power_in"))
      (node (ref "DD7") (pin "2") (pinfunction "GND_2") (pintype "power_in"))
      (node (ref "DD8") (pin "2") (pinfunction "GND_2") (pintype "power_in"))
      (node (ref "DD8") (pin "5") (pinfunction "DIR_5") (pintype "input"))
      (node (ref "FV1") (pin "2") (pinfunction "GND_2") (pintype "passive"))
      (node (ref "R11") (pin "2") (pinfunction "2_2") (pintype "passive"))
      (node (ref "R15") (pin "1") (pinfunction "1_1") (pintype "passive"))
      (node (ref "R17") (pin "1") (pinfunction "1_1") (pintype "passive"))
      (node (ref "R2") (pin "1") (pinfunction "1_1") (pintype "passive"))
      (node (ref "R3") (pin "1") (pinfunction "1_1") (pintype "passive"))
      (node (ref "R36") (pin "1") (pinfunction "1_1") (pintype "passive"))
      (node (ref "R37") (pin "1") (pinfunction "1_1") (pintype "passive"))
      (node (ref "R38") (pin "1") (pinfunction "1_1") (pintype "passive"))
      (node (ref "R39") (pin "1") (pinfunction "1_1") (pintype "passive"))
      (node (ref "R4") (pin "1") (pinfunction "1_1") (pintype "passive"))
      (node (ref "R40") (pin "1") (pinfunction "1_1") (pintype "passive"))
      (node (ref "R41") (pin "1") (pinfunction "1_1") (pintype "passive"))
      (node (ref "R6") (pin "1") (pinfunction "1_1") (pintype "passive"))
      (node (ref "R7") (pin "1") (pinfunction "1_1") (pintype "passive"))
      (node (ref "VT1") (pin "3") (pinfunction "S_3") (pintype "passive"))
      (node (ref "XP1") (pin "4") (pinfunction "GND_4") (pintype "passive"))
      (node (ref "XP2") (pin "4") (pintype "passive"))
      (node (ref "XP3") (pin "3") (pintype "passive"))
      (node (ref "XP3") (pin "5") (pintype "passive"))
      (node (ref "XP3") (pin "9") (pintype "passive"))
      (node (ref "XS1") (pin "A1") (pinfunction "GND_A1") (pintype "passive"))
      (node (ref "XS1") (pin "A12") (pinfunction "GND_A12") (pintype "passive"))
      (node (ref "XS1") (pin "B1") (pinfunction "GND_B1") (pintype "passive"))
      (node (ref "XS1") (pin "B12") (pinfunction "GND_B12") (pintype "passive"))
      (node (ref "XS2") (pin "3") (pintype "passive"))
      (node (ref "XS2") (pin "5") (pintype "passive"))
      (node (ref "XS2") (pin "9") (pintype "passive"))
      (node (ref "XS3") (pin "2") (pintype "passive"))
      (node (ref "XS3") (pin "5") (pintype "passive"))
    )
    (net (code "42") (name "Net-(C8-Pad2)") (class "Default")
      (node (ref "C8") (pin "2") (pinfunction "2_2") (pintype "passive"))
      (node (ref "DD1") (pin "31") (pinfunction "VCAP_31") (pintype "power_in"))
    )
    (net (code "43") (name "Net-(C9-Pad2)") (class "Default")
      (node (ref "C9") (pin "2") (pinfunction "2_2") (pintype "passive"))
      (node (ref "DD1") (pin "47") (pinfunction "VCAP_47") (pintype "power_in"))
    )
    (net (code "44") (name "Net-(DA1-FB)") (class "Default")
      (node (ref "DA1") (pin "3") (pinfunction "FB_3") (pintype "input"))
      (node (ref "R10") (pin "1") (pinfunction "1_1") (pintype "passive"))
      (node (ref "R4") (pin "2") (pinfunction "2_2") (pintype "passive"))
    )
    (net (code "45") (name "Net-(DD1A-PH0{slash}OSCI)") (class "Default")
      (node (ref "C18") (pin "2") (pinfunction "2_2") (pintype "passive"))
      (node (ref "DD1") (pin "5") (pinfunction "PH0/OSCI_5") (pintype "bidirectional"))
      (node (ref "ZQ1") (pin "3") (pinfunction "3_3") (pintype "passive"))
    )
    (net (code "46") (name "Net-(DD1A-PH1{slash}OSCO)") (class "Default")
      (node (ref "C14") (pin "2") (pinfunction "2_2") (pintype "passive"))
      (node (ref "DD1") (pin "6") (pinfunction "PH1/OSCO_6") (pintype "bidirectional"))
      (node (ref "ZQ1") (pin "1") (pinfunction "1_1") (pintype "passive"))
    )
    (net (code "47") (name "Net-(DD2-B1)") (class "Default")
      (node (ref "DD2") (pin "7") (pinfunction "B1_7") (pintype "bidirectional"))
      (node (ref "R26") (pin "1") (pinfunction "1_1") (pintype "passive"))
    )
    (net (code "48") (name "Net-(DD2-B2)") (class "Default")
      (node (ref "DD2") (pin "6") (pinfunction "B2_6") (pintype "bidirectional"))
      (node (ref "R27") (pin "1") (pinfunction "1_1") (pintype "passive"))
    )
    (net (code "49") (name "Net-(DD3-A1)") (class "Default")
      (node (ref "DD3") (pin "2") (pinfunction "A1_2") (pintype "bidirectional"))
      (node (ref "R21") (pin "2") (pinfunction "2_2") (pintype "passive"))
    )
    (net (code "50") (name "Net-(DD3-A2)") (class "Default")
      (node (ref "DD3") (pin "3") (pinfunction "A2_3") (pintype "bidirectional"))
      (node (ref "R22") (pin "2") (pinfunction "2_2") (pintype "passive"))
    )
    (net (code "51") (name "Net-(DD3-B1)") (class "Default")
      (node (ref "DD3") (pin "7") (pinfunction "B1_7") (pintype "bidirectional"))
      (node (ref "R28") (pin "1") (pinfunction "1_1") (pintype "passive"))
    )
    (net (code "52") (name "Net-(DD3-B2)") (class "Default")
      (node (ref "DD3") (pin "6") (pinfunction "B2_6") (pintype "bidirectional"))
      (node (ref "R29") (pin "1") (pinfunction "1_1") (pintype "passive"))
    )
    (net (code "53") (name "Net-(DD4-B1)") (class "Default")
      (node (ref "DD4") (pin "7") (pinfunction "B1_7") (pintype "bidirectional"))
      (node (ref "R30") (pin "1") (pinfunction "1_1") (pintype "passive"))
    )
    (net (code "54") (name "Net-(DD4-B2)") (class "Default")
      (node (ref "DD4") (pin "6") (pinfunction "B2_6") (pintype "bidirectional"))
      (node (ref "R31") (pin "1") (pinfunction "1_1") (pintype "passive"))
    )
    (net (code "55") (name "Net-(DD5-A)") (class "Default")
      (node (ref "DD5") (pin "3") (pinfunction "A_3") (pintype "bidirectional"))
      (node (ref "R23") (pin "2") (pinfunction "2_2") (pintype "passive"))
    )
    (net (code "56") (name "Net-(DD5-B)") (class "Default")
      (node (ref "DD5") (pin "4") (pinfunction "B_4") (pintype "bidirectional"))
      (node (ref "R32") (pin "1") (pinfunction "1_1") (pintype "passive"))
    )
    (net (code "57") (name "Net-(DD6-A)") (class "Default")
      (node (ref "DD6") (pin "3") (pinfunction "A_3") (pintype "bidirectional"))
      (node (ref "R24") (pin "2") (pinfunction "2_2") (pintype "passive"))
    )
    (net (code "58") (name "Net-(DD6-B)") (class "Default")
      (node (ref "DD6") (pin "4") (pinfunction "B_4") (pintype "bidirectional"))
      (node (ref "R33") (pin "1") (pinfunction "1_1") (pintype "passive"))
    )
    (net (code "59") (name "Net-(DD7-A)") (class "Default")
      (node (ref "DD7") (pin "3") (pinfunction "A_3") (pintype "bidirectional"))
      (node (ref "R25") (pin "2") (pinfunction "2_2") (pintype "passive"))
    )
    (net (code "60") (name "Net-(DD7-B)") (class "Default")
      (node (ref "DD7") (pin "4") (pinfunction "B_4") (pintype "bidirectional"))
      (node (ref "R34") (pin "1") (pinfunction "1_1") (pintype "passive"))
    )
    (net (code "61") (name "Net-(DD8-B)") (class "Default")
      (node (ref "DD8") (pin "4") (pinfunction "B_4") (pintype "bidirectional"))
      (node (ref "R35") (pin "1") (pinfunction "1_1") (pintype "passive"))
    )
    (net (code "62") (name "Net-(HL1-К)") (class "Default")
      (node (ref "HL1") (pin "2") (pinfunction "К_2") (pintype "passive"))
      (node (ref "R8") (pin "1") (pinfunction "1_1") (pintype "passive"))
    )
    (net (code "63") (name "Net-(HL2-К)") (class "Default")
      (node (ref "HL2") (pin "2") (pinfunction "К_2") (pintype "passive"))
      (node (ref "R9") (pin "1") (pinfunction "1_1") (pintype "passive"))
    )
    (net (code "64") (name "Net-(VT1-D)") (class "Default")
      (node (ref "R19") (pin "1") (pinfunction "1_1") (pintype "passive"))
      (node (ref "VT1") (pin "2") (pinfunction "D_2") (pintype "passive"))
    )
    (net (code "65") (name "Net-(XS1-CC1)") (class "Default")
      (node (ref "R3") (pin "2") (pinfunction "2_2") (pintype "passive"))
      (node (ref "XS1") (pin "A5") (pinfunction "CC1_A5") (pintype "passive"))
    )
    (net (code "66") (name "Net-(XS1-CC2)") (class "Default")
      (node (ref "R2") (pin "2") (pinfunction "2_2") (pintype "passive"))
      (node (ref "XS1") (pin "B5") (pinfunction "CC2_B5") (pintype "passive"))
    )
    (net (code "67") (name "SHLD") (class "Default")
      (node (ref "C4") (pin "2") (pinfunction "2_2") (pintype "passive"))
      (node (ref "R11") (pin "1") (pinfunction "1_1") (pintype "passive"))
      (node (ref "XP1") (pin "SH") (pinfunction "КОРПУС_SH") (pintype "passive"))
      (node (ref "XS1") (pin "SH") (pinfunction "КОРПУС_SH") (pintype "passive"))
    )
    (net (code "68") (name "TVCC") (class "Default")
      (node (ref "L2") (pin "2") (pinfunction "2_2") (pintype "passive"))
      (node (ref "XP3") (pin "1") (pintype "passive"))
      (node (ref "XS2") (pin "1") (pintype "passive"))
      (node (ref "XS3") (pin "1") (pintype "passive"))
    )
    (net (code "69") (name "VBUS") (class "Default")
      (node (ref "L1") (pin "1") (pinfunction "1_1") (pintype "passive"))
      (node (ref "XP1") (pin "1") (pinfunction "VBUS_1") (pintype "passive"))
      (node (ref "XS1") (pin "A4") (pinfunction "VBUS_A4") (pintype "passive"))
      (node (ref "XS1") (pin "A9") (pinfunction "VBUS_A9") (pintype "passive"))
      (node (ref "XS1") (pin "B4") (pinfunction "VBUS_B4") (pintype "passive"))
      (node (ref "XS1") (pin "B9") (pinfunction "VBUS_B9") (pintype "passive"))
    )
    (net (code "70") (name "VCC3P3") (class "Default")
      (node (ref "C11") (pin "2") (pinfunction "2_2") (pintype "passive"))
      (node (ref "C12") (pin "1") (pinfunction "1_1") (pintype "passive"))
      (node (ref "C13") (pin "1") (pinfunction "1_1") (pintype "passive"))
      (node (ref "C15") (pin "1") (pinfunction "1_1") (pintype "passive"))
      (node (ref "C16") (pin "1") (pinfunction "1_1") (pintype "passive"))
      (node (ref "C17") (pin "1") (pinfunction "1_1") (pintype "passive"))
      (node (ref "C19") (pin "1") (pinfunction "1_1") (pintype "passive"))
      (node (ref "C20") (pin "1") (pinfunction "1_1") (pintype "passive"))
      (node (ref "C21") (pin "1") (pinfunction "1_1") (pintype "passive"))
      (node (ref "C22") (pin "1") (pinfunction "1_1") (pintype "passive"))
      (node (ref "C5") (pin "2") (pinfunction "2_2") (pintype "passive"))
      (node (ref "C6") (pin "2") (pinfunction "2_2") (pintype "passive"))
      (node (ref "DA1") (pin "1") (pinfunction "OUT_1") (pintype "power_in"))
      (node (ref "DD1") (pin "1") (pinfunction "VBAT_1") (pintype "power_in"))
      (node (ref "DD1") (pin "13") (pinfunction "VDDA_13") (pintype "power_in"))
      (node (ref "DD1") (pin "19") (pinfunction "VDD_19") (pintype "power_in"))
      (node (ref "DD1") (pin "32") (pinfunction "VDD_32") (pintype "power_in"))
      (node (ref "DD1") (pin "48") (pinfunction "VDD_48") (pintype "power_in"))
      (node (ref "DD1") (pin "64") (pinfunction "VDD_64") (pintype "power_in"))
      (node (ref "DD2") (pin "1") (pinfunction "VCCA_1") (pintype "power_in"))
      (node (ref "DD3") (pin "1") (pinfunction "VCCA_1") (pintype "power_in"))
      (node (ref "DD4") (pin "1") (pinfunction "VCCA_1") (pintype "power_in"))
      (node (ref "DD5") (pin "1") (pinfunction "VCCA_1") (pintype "power_in"))
      (node (ref "DD6") (pin "1") (pinfunction "VCCA_1") (pintype "power_in"))
      (node (ref "DD7") (pin "1") (pinfunction "VCCA_1") (pintype "power_in"))
      (node (ref "DD8") (pin "1") (pinfunction "VCCA_1") (pintype "power_in"))
      (node (ref "HL1") (pin "1") (pinfunction "А_1") (pintype "passive"))
      (node (ref "HL2") (pin "1") (pinfunction "А_1") (pintype "passive"))
      (node (ref "R1") (pin "2") (pinfunction "2_2") (pintype "passive"))
      (node (ref "R10") (pin "2") (pinfunction "2_2") (pintype "passive"))
      (node (ref "R5") (pin "1") (pinfunction "1_1") (pintype "passive"))
      (node (ref "XP2") (pin "1") (pintype "passive"))
    )
    (net (code "71") (name "VCC5P0") (class "Default")
      (node (ref "C1") (pin "2") (pinfunction "2_2") (pintype "passive"))
      (node (ref "C3") (pin "2") (pinfunction "2_2") (pintype "passive"))
      (node (ref "DA1") (pin "5") (pinfunction "EN_5") (pintype "input"))
      (node (ref "DA1") (pin "8") (pinfunction "IN_8") (pintype "power_in"))
      (node (ref "FV1") (pin "5") (pinfunction "VBUS_5") (pintype "passive"))
      (node (ref "L1") (pin "2") (pinfunction "2_2") (pintype "passive"))
      (node (ref "R16") (pin "2") (pinfunction "2_2") (pintype "passive"))
    )
    (net (code "72") (name "unconnected-(DD1A-PA9-Pad42)") (class "Default")
      (node (ref "DD1") (pin "42") (pinfunction "PA9_42") (pintype "bidirectional+no_connect"))
    )
    (net (code "73") (name "unconnected-(DD1A-PA15-Pad50)") (class "Default")
      (node (ref "DD1") (pin "50") (pinfunction "PA15_50") (pintype "bidirectional+no_connect"))
    )
    (net (code "74") (name "unconnected-(DD1A-PB0-Pad26)") (class "Default")
      (node (ref "DD1") (pin "26") (pinfunction "PB0_26") (pintype "bidirectional+no_connect"))
    )
    (net (code "75") (name "unconnected-(DD1A-PB3{slash}SWO-Pad55)") (class "Default")
      (node (ref "DD1") (pin "55") (pinfunction "PB3/SWO_55") (pintype "bidirectional+no_connect"))
    )
    (net (code "76") (name "unconnected-(DD1A-PB4-Pad56)") (class "Default")
      (node (ref "DD1") (pin "56") (pinfunction "PB4_56") (pintype "bidirectional+no_connect"))
    )
    (net (code "77") (name "unconnected-(DD1A-PB5-Pad57)") (class "Default")
      (node (ref "DD1") (pin "57") (pinfunction "PB5_57") (pintype "bidirectional+no_connect"))
    )
    (net (code "78") (name "unconnected-(DD1A-PB6-Pad58)") (class "Default")
      (node (ref "DD1") (pin "58") (pinfunction "PB6_58") (pintype "bidirectional+no_connect"))
    )
    (net (code "79") (name "unconnected-(DD1A-PB7-Pad59)") (class "Default")
      (node (ref "DD1") (pin "59") (pinfunction "PB7_59") (pintype "bidirectional+no_connect"))
    )
    (net (code "80") (name "unconnected-(DD1A-PB9-Pad62)") (class "Default")
      (node (ref "DD1") (pin "62") (pinfunction "PB9_62") (pintype "bidirectional+no_connect"))
    )
    (net (code "81") (name "unconnected-(DD1A-PC4-Pad24)") (class "Default")
      (node (ref "DD1") (pin "24") (pinfunction "PC4_24") (pintype "bidirectional+no_connect"))
    )
    (net (code "82") (name "unconnected-(DD1A-PC10-Pad51)") (class "Default")
      (node (ref "DD1") (pin "51") (pinfunction "PC10_51") (pintype "bidirectional+no_connect"))
    )
    (net (code "83") (name "unconnected-(DD1A-PC11-Pad52)") (class "Default")
      (node (ref "DD1") (pin "52") (pinfunction "PC11_52") (pintype "bidirectional+no_connect"))
    )
    (net (code "84") (name "unconnected-(DD1A-PC13{slash}RTC-Pad2)") (class "Default")
      (node (ref "DD1") (pin "2") (pinfunction "PC13/RTC_2") (pintype "bidirectional+no_connect"))
    )
    (net (code "85") (name "unconnected-(DD1A-PC14{slash}OSC3I-Pad3)") (class "Default")
      (node (ref "DD1") (pin "3") (pinfunction "PC14/OSC3I_3") (pintype "bidirectional+no_connect"))
    )
    (net (code "86") (name "unconnected-(DD1A-PC15{slash}OSC3O-Pad4)") (class "Default")
      (node (ref "DD1") (pin "4") (pinfunction "PC15/OSC3O_4") (pintype "bidirectional+no_connect"))
    )
    (net (code "87") (name "unconnected-(DD1A-PD2-Pad54)") (class "Default")
      (node (ref "DD1") (pin "54") (pinfunction "PD2_54") (pintype "bidirectional+no_connect"))
    )
    (net (code "88") (name "unconnected-(XS1-SBU1-PadA8)") (class "Default")
      (node (ref "XS1") (pin "A8") (pinfunction "SBU1_A8") (pintype "passive+no_connect"))
    )
    (net (code "89") (name "unconnected-(XS1-SBU2-PadB8)") (class "Default")
      (node (ref "XS1") (pin "B8") (pinfunction "SBU2_B8") (pintype "passive+no_connect"))
    )
    (net (code "90") (name "unconnected-(XS3-Pad6)") (class "Default")
      (node (ref "XS3") (pin "6") (pintype "passive+no_connect"))
    )
  )
)
